# SCH_PCB-BRAILLE_2026-09-01.net
KiCad netlist of a schematic drawn in EasyEDA
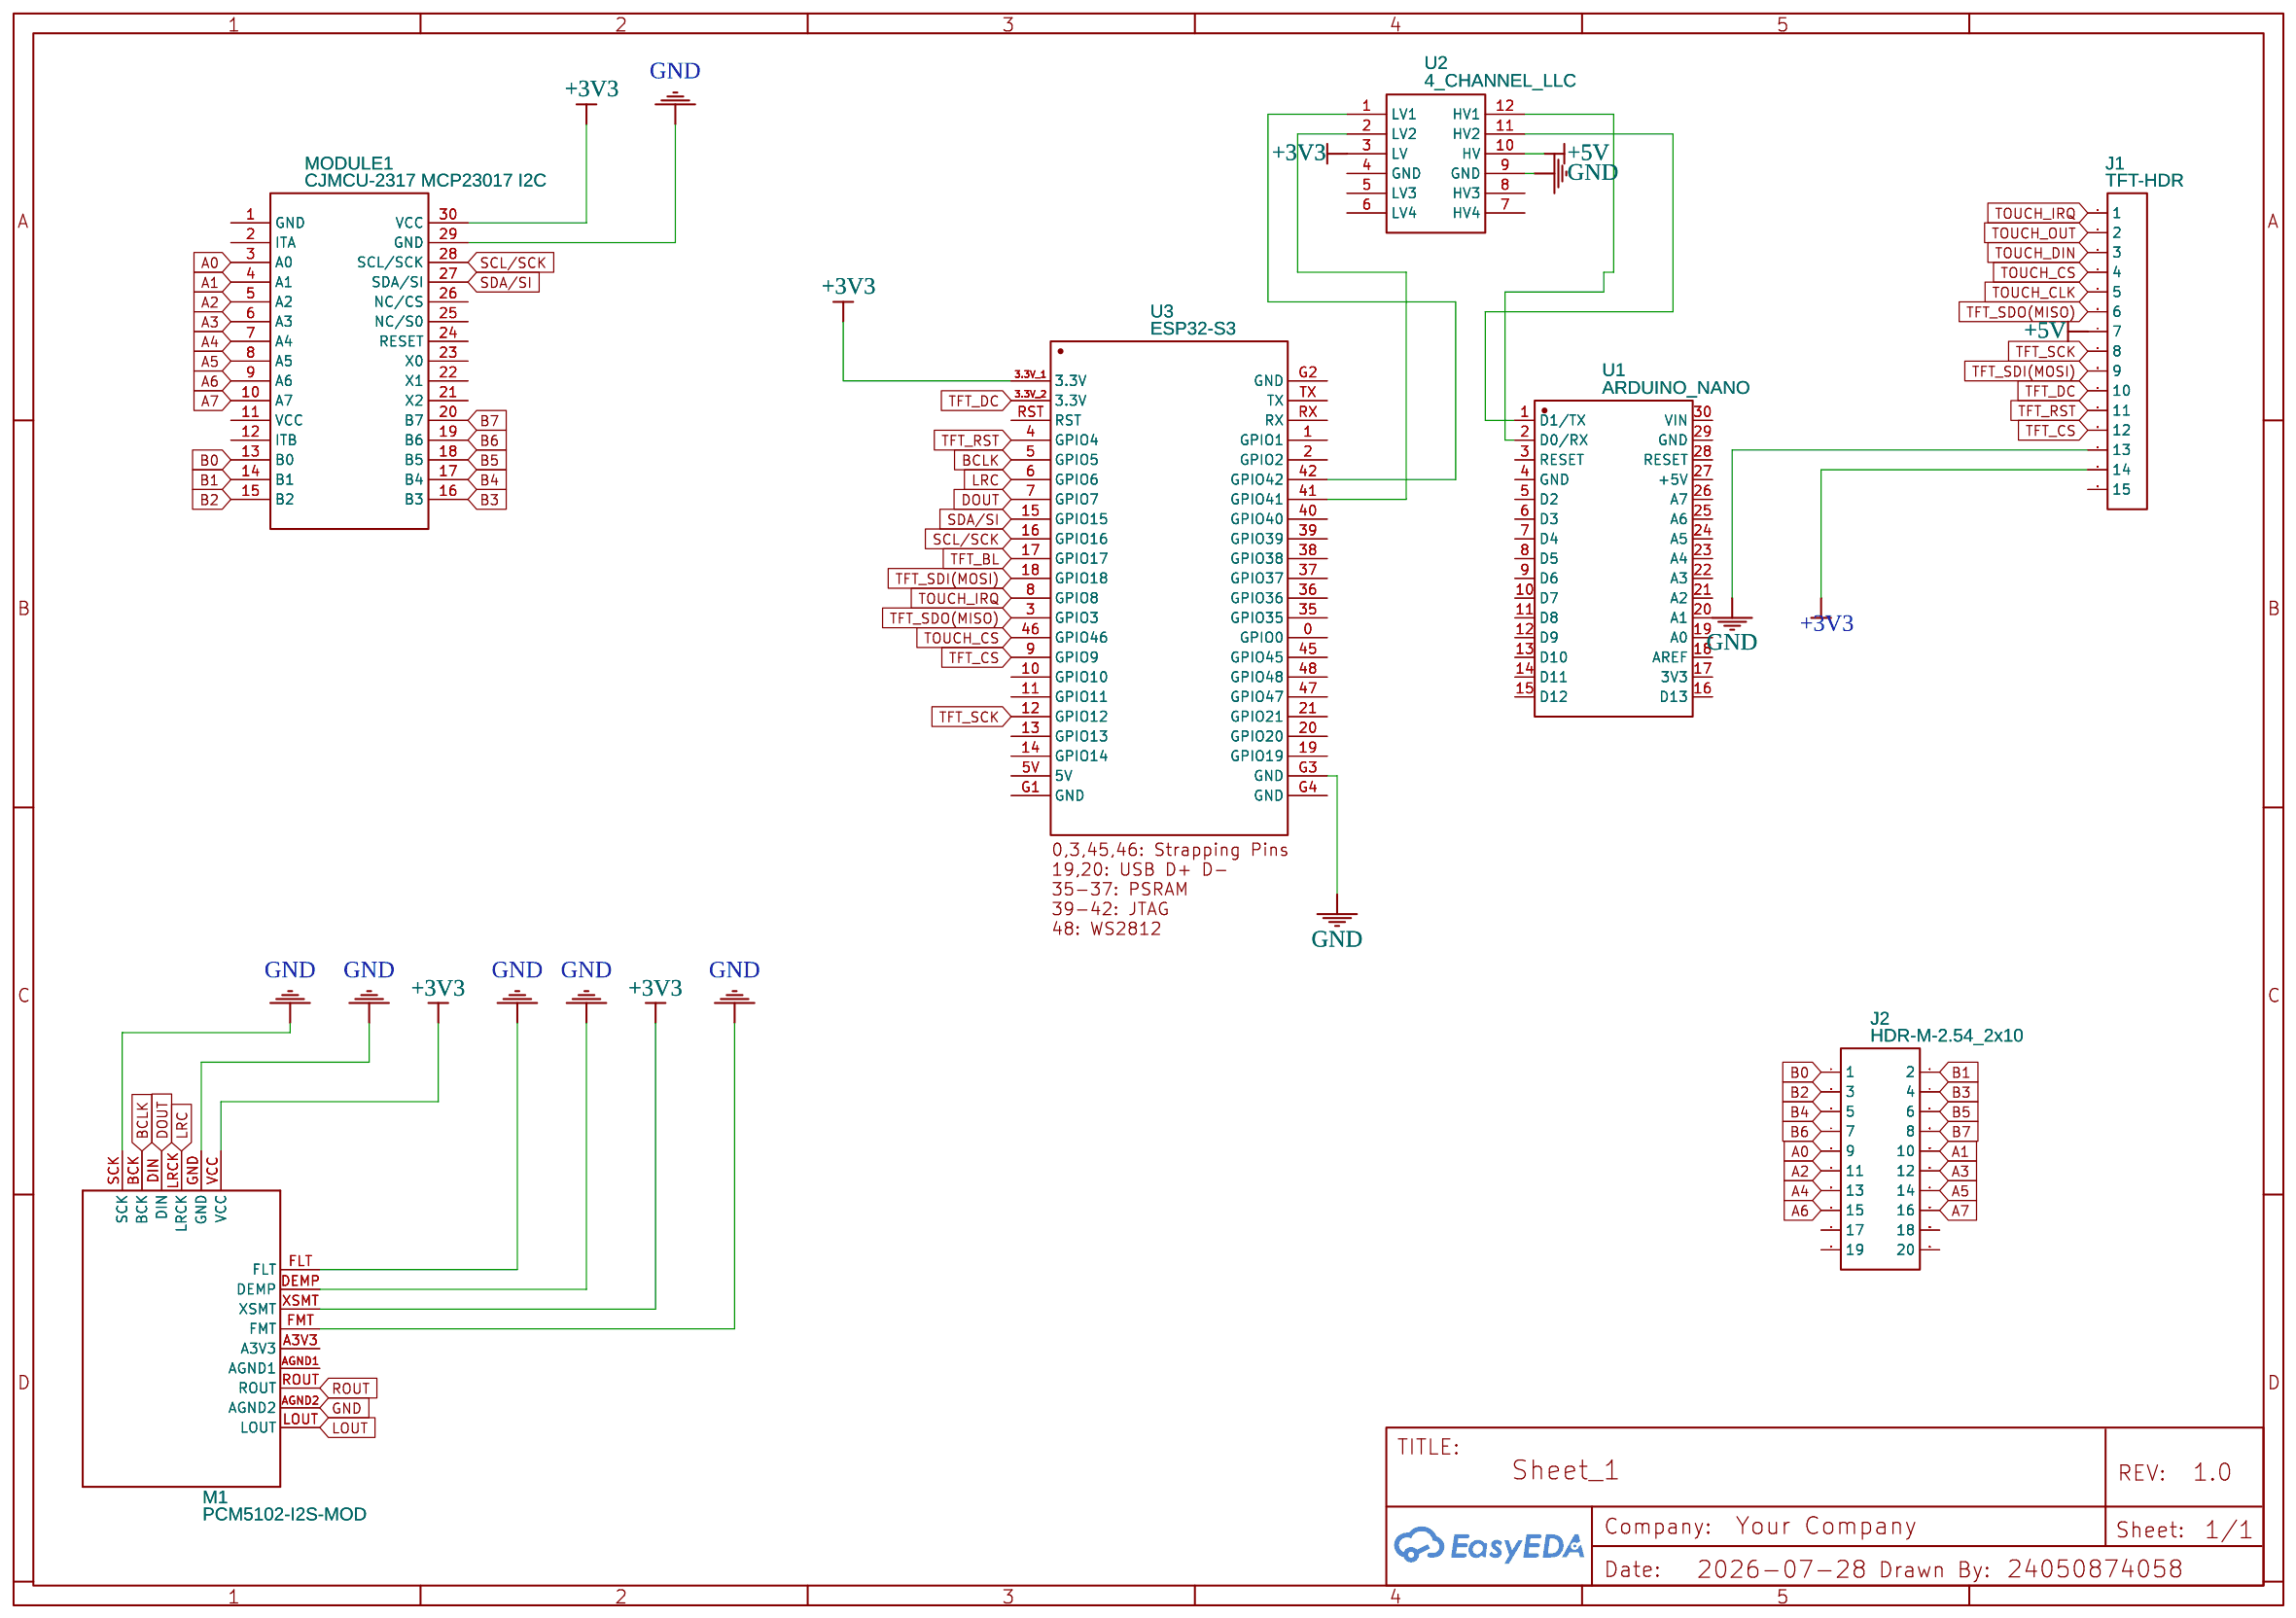
[diagram p0: schematic sheet]

(export (version "E")
  (design (tool "Eeschema 10.0.6"))
  (components
    (comp (ref "J1") (value "TFT-HDR") (libsource (lib "") (part "HDR-M-2.54_1x15")))
    (comp (ref "J2") (value "HDR-M-2.54_2x10") (libsource (lib "") (part "HDR-M-2.54_2x10")))
    (comp (ref "M1") (value "PCM5102-I2S-MOD") (libsource (lib "") (part "PCM5102-I2S-MOD")))
    (comp (ref "MODULE1")
      (value "CJMCU-2317 MCP23017 I2C")
      (libsource (lib "") (part "CJMCU-2317 MCP23017 I2C Serial Interface 16 bit I/O Expander Serial Module"))
    )
    (comp (ref "U1") (value "ARDUINO_NANO") (libsource (lib "") (part "ARDUINO_NANO")))
    (comp (ref "U2") (value "4_CHANNEL_LLC") (libsource (lib "") (part "4_CHANNEL_LLC")))
    (comp (ref "U3") (value "ESP32-S3") (libsource (lib "") (part "ESP32-S3")))
  )
  (nets
    (net (code "1") (name "+3V3") (class "Default")
      (node (ref "J1") (pin "14") (pinfunction "14_14") (pintype "unspecified"))
      (node (ref "M1") (pin "VCC") (pinfunction "VCC_VCC") (pintype "bidirectional"))
      (node (ref "M1") (pin "XSMT") (pinfunction "XSMT_XSMT") (pintype "bidirectional"))
      (node (ref "MODULE1") (pin "30") (pinfunction "VCC_30") (pintype "unspecified"))
      (node (ref "U2") (pin "3") (pinfunction "LV_3") (pintype "unspecified"))
      (node (ref "U3") (pin "3.3V_1") (pinfunction "3.3V_3.3V_1") (pintype "bidirectional"))
    )
    (net (code "2") (name "+5V") (class "Default")
      (node (ref "J1") (pin "7") (pinfunction "7_7") (pintype "unspecified"))
      (node (ref "U2") (pin "10") (pinfunction "HV_10") (pintype "unspecified"))
    )
    (net (code "3") (name "A0") (class "Default")
      (node (ref "J2") (pin "9") (pinfunction "9_9") (pintype "unspecified"))
      (node (ref "MODULE1") (pin "3") (pinfunction "A0_3") (pintype "unspecified"))
    )
    (net (code "4") (name "A1") (class "Default")
      (node (ref "J2") (pin "10") (pinfunction "10_10") (pintype "unspecified"))
      (node (ref "MODULE1") (pin "4") (pinfunction "A1_4") (pintype "unspecified"))
    )
    (net (code "5") (name "A2") (class "Default")
      (node (ref "J2") (pin "11") (pinfunction "11_11") (pintype "unspecified"))
      (node (ref "MODULE1") (pin "5") (pinfunction "A2_5") (pintype "unspecified"))
    )
    (net (code "6") (name "A3") (class "Default")
      (node (ref "J2") (pin "12") (pinfunction "12_12") (pintype "unspecified"))
      (node (ref "MODULE1") (pin "6") (pinfunction "A3_6") (pintype "unspecified"))
    )
    (net (code "7") (name "A4") (class "Default")
      (node (ref "J2") (pin "13") (pinfunction "13_13") (pintype "unspecified"))
      (node (ref "MODULE1") (pin "7") (pinfunction "A4_7") (pintype "unspecified"))
    )
    (net (code "8") (name "A5") (class "Default")
      (node (ref "J2") (pin "14") (pinfunction "14_14") (pintype "unspecified"))
      (node (ref "MODULE1") (pin "8") (pinfunction "A5_8") (pintype "unspecified"))
    )
    (net (code "9") (name "A6") (class "Default")
      (node (ref "J2") (pin "15") (pinfunction "15_15") (pintype "unspecified"))
      (node (ref "MODULE1") (pin "9") (pinfunction "A6_9") (pintype "unspecified"))
    )
    (net (code "10") (name "A7") (class "Default")
      (node (ref "J2") (pin "16") (pinfunction "16_16") (pintype "unspecified"))
      (node (ref "MODULE1") (pin "10") (pinfunction "A7_10") (pintype "unspecified"))
    )
    (net (code "11") (name "B0") (class "Default")
      (node (ref "J2") (pin "1") (pinfunction "1_1") (pintype "unspecified"))
      (node (ref "MODULE1") (pin "13") (pinfunction "B0_13") (pintype "unspecified"))
    )
    (net (code "12") (name "B1") (class "Default")
      (node (ref "J2") (pin "2") (pinfunction "2_2") (pintype "unspecified"))
      (node (ref "MODULE1") (pin "14") (pinfunction "B1_14") (pintype "unspecified"))
    )
    (net (code "13") (name "B2") (class "Default")
      (node (ref "J2") (pin "3") (pinfunction "3_3") (pintype "unspecified"))
      (node (ref "MODULE1") (pin "15") (pinfunction "B2_15") (pintype "unspecified"))
    )
    (net (code "14") (name "B3") (class "Default")
      (node (ref "J2") (pin "4") (pinfunction "4_4") (pintype "unspecified"))
      (node (ref "MODULE1") (pin "16") (pinfunction "B3_16") (pintype "unspecified"))
    )
    (net (code "15") (name "B4") (class "Default")
      (node (ref "J2") (pin "5") (pinfunction "5_5") (pintype "unspecified"))
      (node (ref "MODULE1") (pin "17") (pinfunction "B4_17") (pintype "unspecified"))
    )
    (net (code "16") (name "B5") (class "Default")
      (node (ref "J2") (pin "6") (pinfunction "6_6") (pintype "unspecified"))
      (node (ref "MODULE1") (pin "18") (pinfunction "B5_18") (pintype "unspecified"))
    )
    (net (code "17") (name "B6") (class "Default")
      (node (ref "J2") (pin "7") (pinfunction "7_7") (pintype "unspecified"))
      (node (ref "MODULE1") (pin "19") (pinfunction "B6_19") (pintype "unspecified"))
    )
    (net (code "18") (name "B7") (class "Default")
      (node (ref "J2") (pin "8") (pinfunction "8_8") (pintype "unspecified"))
      (node (ref "MODULE1") (pin "20") (pinfunction "B7_20") (pintype "unspecified"))
    )
    (net (code "19") (name "BCLK") (class "Default")
      (node (ref "M1") (pin "BCK") (pinfunction "BCK_BCK") (pintype "bidirectional"))
      (node (ref "U3") (pin "5") (pinfunction "GPIO5_5") (pintype "bidirectional"))
    )
    (net (code "20") (name "DOUT") (class "Default")
      (node (ref "M1") (pin "DIN") (pinfunction "DIN_DIN") (pintype "bidirectional"))
      (node (ref "U3") (pin "7") (pinfunction "GPIO7_7") (pintype "bidirectional"))
    )
    (net (code "21") (name "GND") (class "Default")
      (node (ref "J1") (pin "13") (pinfunction "13_13") (pintype "unspecified"))
      (node (ref "M1") (pin "AGND2") (pinfunction "AGND2_AGND2") (pintype "bidirectional"))
      (node (ref "M1") (pin "DEMP") (pinfunction "DEMP_DEMP") (pintype "bidirectional"))
      (node (ref "M1") (pin "FLT") (pinfunction "FLT_FLT") (pintype "bidirectional"))
      (node (ref "M1") (pin "FMT") (pinfunction "FMT_FMT") (pintype "bidirectional"))
      (node (ref "M1") (pin "GND") (pinfunction "GND_GND") (pintype "bidirectional"))
      (node (ref "M1") (pin "SCK") (pinfunction "SCK_SCK") (pintype "bidirectional"))
      (node (ref "MODULE1") (pin "29") (pinfunction "GND_29") (pintype "unspecified"))
      (node (ref "U2") (pin "9") (pinfunction "GND_9") (pintype "unspecified"))
      (node (ref "U3") (pin "G3") (pinfunction "GND_G3") (pintype "bidirectional"))
    )
    (net (code "22") (name "LOUT") (class "Default")
      (node (ref "M1") (pin "LOUT") (pinfunction "LOUT_LOUT") (pintype "bidirectional"))
    )
    (net (code "23") (name "LRC") (class "Default")
      (node (ref "M1") (pin "LRCK") (pinfunction "LRCK_LRCK") (pintype "bidirectional"))
      (node (ref "U3") (pin "6") (pinfunction "GPIO6_6") (pintype "bidirectional"))
    )
    (net (code "24") (name "Net-(U1-D0{slash}RX)") (class "Default")
      (node (ref "U1") (pin "2") (pinfunction "D0/RX_2") (pintype "unspecified"))
      (node (ref "U2") (pin "12") (pinfunction "HV1_12") (pintype "unspecified"))
    )
    (net (code "25") (name "Net-(U1-D1{slash}TX)") (class "Default")
      (node (ref "U1") (pin "1") (pinfunction "D1/TX_1") (pintype "unspecified"))
      (node (ref "U2") (pin "11") (pinfunction "HV2_11") (pintype "unspecified"))
    )
    (net (code "26") (name "Net-(U2-LV1)") (class "Default")
      (node (ref "U2") (pin "1") (pinfunction "LV1_1") (pintype "unspecified"))
      (node (ref "U3") (pin "42") (pinfunction "GPIO42_42") (pintype "bidirectional"))
    )
    (net (code "27") (name "Net-(U2-LV2)") (class "Default")
      (node (ref "U2") (pin "2") (pinfunction "LV2_2") (pintype "unspecified"))
      (node (ref "U3") (pin "41") (pinfunction "GPIO41_41") (pintype "bidirectional"))
    )
    (net (code "28") (name "ROUT") (class "Default")
      (node (ref "M1") (pin "ROUT") (pinfunction "ROUT_ROUT") (pintype "bidirectional"))
    )
    (net (code "29") (name "SCL{slash}SCK") (class "Default")
      (node (ref "MODULE1") (pin "28") (pinfunction "SCL/SCK_28") (pintype "unspecified"))
      (node (ref "U3") (pin "16") (pinfunction "GPIO16_16") (pintype "bidirectional"))
    )
    (net (code "30") (name "SDA{slash}SI") (class "Default")
      (node (ref "MODULE1") (pin "27") (pinfunction "SDA/SI_27") (pintype "unspecified"))
      (node (ref "U3") (pin "15") (pinfunction "GPIO15_15") (pintype "bidirectional"))
    )
    (net (code "31") (name "TFT_BL") (class "Default")
      (node (ref "U3") (pin "17") (pinfunction "GPIO17_17") (pintype "bidirectional"))
    )
    (net (code "32") (name "TFT_CS") (class "Default")
      (node (ref "J1") (pin "12") (pinfunction "12_12") (pintype "unspecified"))
      (node (ref "U3") (pin "9") (pinfunction "GPIO9_9") (pintype "bidirectional"))
    )
    (net (code "33") (name "TFT_DC") (class "Default")
      (node (ref "J1") (pin "10") (pinfunction "10_10") (pintype "unspecified"))
      (node (ref "U3") (pin "3.3V_2") (pinfunction "3.3V_3.3V_2") (pintype "bidirectional"))
    )
    (net (code "34") (name "TFT_RST") (class "Default")
      (node (ref "J1") (pin "11") (pinfunction "11_11") (pintype "unspecified"))
      (node (ref "U3") (pin "4") (pinfunction "GPIO4_4") (pintype "bidirectional"))
    )
    (net (code "35") (name "TFT_SCK") (class "Default")
      (node (ref "J1") (pin "8") (pinfunction "8_8") (pintype "unspecified"))
      (node (ref "U3") (pin "12") (pinfunction "GPIO12_12") (pintype "bidirectional"))
    )
    (net (code "36") (name "TFT_SDI(MOSI)") (class "Default")
      (node (ref "J1") (pin "9") (pinfunction "9_9") (pintype "unspecified"))
      (node (ref "U3") (pin "18") (pinfunction "GPIO18_18") (pintype "bidirectional"))
    )
    (net (code "37") (name "TFT_SDO(MISO)") (class "Default")
      (node (ref "J1") (pin "6") (pinfunction "6_6") (pintype "unspecified"))
      (node (ref "U3") (pin "3") (pinfunction "GPIO3_3") (pintype "bidirectional"))
    )
    (net (code "38") (name "TOUCH_CLK") (class "Default")
      (node (ref "J1") (pin "5") (pinfunction "5_5") (pintype "unspecified"))
    )
    (net (code "39") (name "TOUCH_CS") (class "Default")
      (node (ref "J1") (pin "4") (pinfunction "4_4") (pintype "unspecified"))
      (node (ref "U3") (pin "46") (pinfunction "GPIO46_46") (pintype "bidirectional"))
    )
    (net (code "40") (name "TOUCH_DIN") (class "Default")
      (node (ref "J1") (pin "3") (pinfunction "3_3") (pintype "unspecified"))
    )
    (net (code "41") (name "TOUCH_IRQ") (class "Default")
      (node (ref "J1") (pin "1") (pinfunction "1_1") (pintype "unspecified"))
      (node (ref "U3") (pin "8") (pinfunction "GPIO8_8") (pintype "bidirectional"))
    )
    (net (code "42") (name "TOUCH_OUT") (class "Default")
      (node (ref "J1") (pin "2") (pinfunction "2_2") (pintype "unspecified"))
    )
    (net (code "43") (name "unconnected-(J1-Pad15)") (class "Default")
      (node (ref "J1") (pin "15") (pinfunction "15_15") (pintype "unspecified"))
    )
    (net (code "44") (name "unconnected-(J2-Pad17)") (class "Default")
      (node (ref "J2") (pin "17") (pinfunction "17_17") (pintype "unspecified"))
    )
    (net (code "45") (name "unconnected-(J2-Pad18)") (class "Default")
      (node (ref "J2") (pin "18") (pinfunction "18_18") (pintype "unspecified"))
    )
    (net (code "46") (name "unconnected-(J2-Pad19)") (class "Default")
      (node (ref "J2") (pin "19") (pinfunction "19_19") (pintype "unspecified"))
    )
    (net (code "47") (name "unconnected-(J2-Pad20)") (class "Default")
      (node (ref "J2") (pin "20") (pinfunction "20_20") (pintype "unspecified"))
    )
    (net (code "48") (name "unconnected-(M1-PadA3V3)") (class "Default")
      (node (ref "M1") (pin "A3V3") (pinfunction "A3V3_A3V3") (pintype "bidirectional"))
    )
    (net (code "49") (name "unconnected-(M1-PadAGND1)") (class "Default")
      (node (ref "M1") (pin "AGND1") (pinfunction "AGND1_AGND1") (pintype "bidirectional"))
    )
    (net (code "50") (name "unconnected-(MODULE1-GND-Pad1)") (class "Default")
      (node (ref "MODULE1") (pin "1") (pinfunction "GND_1") (pintype "unspecified"))
    )
    (net (code "51") (name "unconnected-(MODULE1-ITA-Pad2)") (class "Default")
      (node (ref "MODULE1") (pin "2") (pinfunction "ITA_2") (pintype "unspecified"))
    )
    (net (code "52") (name "unconnected-(MODULE1-ITB-Pad12)") (class "Default")
      (node (ref "MODULE1") (pin "12") (pinfunction "ITB_12") (pintype "unspecified"))
    )
    (net (code "53") (name "unconnected-(MODULE1-NC{slash}CS-Pad26)") (class "Default")
      (node (ref "MODULE1") (pin "26") (pinfunction "NC/CS_26") (pintype "unspecified"))
    )
    (net (code "54") (name "unconnected-(MODULE1-NC{slash}S0-Pad25)") (class "Default")
      (node (ref "MODULE1") (pin "25") (pinfunction "NC/S0_25") (pintype "unspecified"))
    )
    (net (code "55") (name "unconnected-(MODULE1-RESET-Pad24)") (class "Default")
      (node (ref "MODULE1") (pin "24") (pinfunction "RESET_24") (pintype "unspecified"))
    )
    (net (code "56") (name "unconnected-(MODULE1-VCC-Pad11)") (class "Default")
      (node (ref "MODULE1") (pin "11") (pinfunction "VCC_11") (pintype "unspecified"))
    )
    (net (code "57") (name "unconnected-(MODULE1-X0-Pad23)") (class "Default")
      (node (ref "MODULE1") (pin "23") (pinfunction "X0_23") (pintype "unspecified"))
    )
    (net (code "58") (name "unconnected-(MODULE1-X1-Pad22)") (class "Default")
      (node (ref "MODULE1") (pin "22") (pinfunction "X1_22") (pintype "unspecified"))
    )
    (net (code "59") (name "unconnected-(MODULE1-X2-Pad21)") (class "Default")
      (node (ref "MODULE1") (pin "21") (pinfunction "X2_21") (pintype "unspecified"))
    )
    (net (code "60") (name "unconnected-(U1-+5V-Pad27)") (class "Default")
      (node (ref "U1") (pin "27") (pinfunction "+5V_27") (pintype "unspecified"))
    )
    (net (code "61") (name "unconnected-(U1-3V3-Pad17)") (class "Default")
      (node (ref "U1") (pin "17") (pinfunction "3V3_17") (pintype "unspecified"))
    )
    (net (code "62") (name "unconnected-(U1-A0-Pad19)") (class "Default")
      (node (ref "U1") (pin "19") (pinfunction "A0_19") (pintype "unspecified"))
    )
    (net (code "63") (name "unconnected-(U1-A1-Pad20)") (class "Default")
      (node (ref "U1") (pin "20") (pinfunction "A1_20") (pintype "unspecified"))
    )
    (net (code "64") (name "unconnected-(U1-A2-Pad21)") (class "Default")
      (node (ref "U1") (pin "21") (pinfunction "A2_21") (pintype "unspecified"))
    )
    (net (code "65") (name "unconnected-(U1-A3-Pad22)") (class "Default")
      (node (ref "U1") (pin "22") (pinfunction "A3_22") (pintype "unspecified"))
    )
    (net (code "66") (name "unconnected-(U1-A4-Pad23)") (class "Default")
      (node (ref "U1") (pin "23") (pinfunction "A4_23") (pintype "unspecified"))
    )
    (net (code "67") (name "unconnected-(U1-A5-Pad24)") (class "Default")
      (node (ref "U1") (pin "24") (pinfunction "A5_24") (pintype "unspecified"))
    )
    (net (code "68") (name "unconnected-(U1-A6-Pad25)") (class "Default")
      (node (ref "U1") (pin "25") (pinfunction "A6_25") (pintype "unspecified"))
    )
    (net (code "69") (name "unconnected-(U1-A7-Pad26)") (class "Default")
      (node (ref "U1") (pin "26") (pinfunction "A7_26") (pintype "unspecified"))
    )
    (net (code "70") (name "unconnected-(U1-AREF-Pad18)") (class "Default")
      (node (ref "U1") (pin "18") (pinfunction "AREF_18") (pintype "unspecified"))
    )
    (net (code "71") (name "unconnected-(U1-D2-Pad5)") (class "Default")
      (node (ref "U1") (pin "5") (pinfunction "D2_5") (pintype "unspecified"))
    )
    (net (code "72") (name "unconnected-(U1-D3-Pad6)") (class "Default")
      (node (ref "U1") (pin "6") (pinfunction "D3_6") (pintype "unspecified"))
    )
    (net (code "73") (name "unconnected-(U1-D4-Pad7)") (class "Default")
      (node (ref "U1") (pin "7") (pinfunction "D4_7") (pintype "unspecified"))
    )
    (net (code "74") (name "unconnected-(U1-D5-Pad8)") (class "Default")
      (node (ref "U1") (pin "8") (pinfunction "D5_8") (pintype "unspecified"))
    )
    (net (code "75") (name "unconnected-(U1-D6-Pad9)") (class "Default")
      (node (ref "U1") (pin "9") (pinfunction "D6_9") (pintype "unspecified"))
    )
    (net (code "76") (name "unconnected-(U1-D7-Pad10)") (class "Default")
      (node (ref "U1") (pin "10") (pinfunction "D7_10") (pintype "unspecified"))
    )
    (net (code "77") (name "unconnected-(U1-D8-Pad11)") (class "Default")
      (node (ref "U1") (pin "11") (pinfunction "D8_11") (pintype "unspecified"))
    )
    (net (code "78") (name "unconnected-(U1-D9-Pad12)") (class "Default")
      (node (ref "U1") (pin "12") (pinfunction "D9_12") (pintype "unspecified"))
    )
    (net (code "79") (name "unconnected-(U1-D10-Pad13)") (class "Default")
      (node (ref "U1") (pin "13") (pinfunction "D10_13") (pintype "unspecified"))
    )
    (net (code "80") (name "unconnected-(U1-D11-Pad14)") (class "Default")
      (node (ref "U1") (pin "14") (pinfunction "D11_14") (pintype "unspecified"))
    )
    (net (code "81") (name "unconnected-(U1-D12-Pad15)") (class "Default")
      (node (ref "U1") (pin "15") (pinfunction "D12_15") (pintype "unspecified"))
    )
    (net (code "82") (name "unconnected-(U1-D13-Pad16)") (class "Default")
      (node (ref "U1") (pin "16") (pinfunction "D13_16") (pintype "unspecified"))
    )
    (net (code "83") (name "unconnected-(U1-GND-Pad4)") (class "Default")
      (node (ref "U1") (pin "4") (pinfunction "GND_4") (pintype "unspecified"))
    )
    (net (code "84") (name "unconnected-(U1-GND-Pad29)") (class "Default")
      (node (ref "U1") (pin "29") (pinfunction "GND_29") (pintype "unspecified"))
    )
    (net (code "85") (name "unconnected-(U1-RESET-Pad3)") (class "Default")
      (node (ref "U1") (pin "3") (pinfunction "RESET_3") (pintype "unspecified"))
    )
    (net (code "86") (name "unconnected-(U1-RESET-Pad28)") (class "Default")
      (node (ref "U1") (pin "28") (pinfunction "RESET_28") (pintype "unspecified"))
    )
    (net (code "87") (name "unconnected-(U1-VIN-Pad30)") (class "Default")
      (node (ref "U1") (pin "30") (pinfunction "VIN_30") (pintype "unspecified"))
    )
    (net (code "88") (name "unconnected-(U2-GND-Pad4)") (class "Default")
      (node (ref "U2") (pin "4") (pinfunction "GND_4") (pintype "unspecified"))
    )
    (net (code "89") (name "unconnected-(U2-HV3-Pad8)") (class "Default")
      (node (ref "U2") (pin "8") (pinfunction "HV3_8") (pintype "unspecified"))
    )
    (net (code "90") (name "unconnected-(U2-HV4-Pad7)") (class "Default")
      (node (ref "U2") (pin "7") (pinfunction "HV4_7") (pintype "unspecified"))
    )
    (net (code "91") (name "unconnected-(U2-LV3-Pad5)") (class "Default")
      (node (ref "U2") (pin "5") (pinfunction "LV3_5") (pintype "unspecified"))
    )
    (net (code "92") (name "unconnected-(U2-LV4-Pad6)") (class "Default")
      (node (ref "U2") (pin "6") (pinfunction "LV4_6") (pintype "unspecified"))
    )
    (net (code "93") (name "unconnected-(U3-GND-PadG1)") (class "Default")
      (node (ref "U3") (pin "G1") (pinfunction "GND_G1") (pintype "bidirectional"))
    )
    (net (code "94") (name "unconnected-(U3-GND-PadG2)") (class "Default")
      (node (ref "U3") (pin "G2") (pinfunction "GND_G2") (pintype "bidirectional"))
    )
    (net (code "95") (name "unconnected-(U3-GND-PadG4)") (class "Default")
      (node (ref "U3") (pin "G4") (pinfunction "GND_G4") (pintype "bidirectional"))
    )
    (net (code "96") (name "unconnected-(U3-GPIO0-Pad0)") (class "Default")
      (node (ref "U3") (pin "0") (pinfunction "GPIO0_0") (pintype "bidirectional"))
    )
    (net (code "97") (name "unconnected-(U3-GPIO1-Pad1)") (class "Default")
      (node (ref "U3") (pin "1") (pinfunction "GPIO1_1") (pintype "bidirectional"))
    )
    (net (code "98") (name "unconnected-(U3-GPIO2-Pad2)") (class "Default")
      (node (ref "U3") (pin "2") (pinfunction "GPIO2_2") (pintype "bidirectional"))
    )
    (net (code "99") (name "unconnected-(U3-GPIO10-Pad10)") (class "Default")
      (node (ref "U3") (pin "10") (pinfunction "GPIO10_10") (pintype "bidirectional"))
    )
    (net (code "100") (name "unconnected-(U3-GPIO11-Pad11)") (class "Default")
      (node (ref "U3") (pin "11") (pinfunction "GPIO11_11") (pintype "bidirectional"))
    )
    (net (code "101") (name "unconnected-(U3-GPIO13-Pad13)") (class "Default")
      (node (ref "U3") (pin "13") (pinfunction "GPIO13_13") (pintype "bidirectional"))
    )
    (net (code "102") (name "unconnected-(U3-GPIO14-Pad14)") (class "Default")
      (node (ref "U3") (pin "14") (pinfunction "GPIO14_14") (pintype "bidirectional"))
    )
    (net (code "103") (name "unconnected-(U3-GPIO19-Pad19)") (class "Default")
      (node (ref "U3") (pin "19") (pinfunction "GPIO19_19") (pintype "bidirectional"))
    )
    (net (code "104") (name "unconnected-(U3-GPIO20-Pad20)") (class "Default")
      (node (ref "U3") (pin "20") (pinfunction "GPIO20_20") (pintype "bidirectional"))
    )
    (net (code "105") (name "unconnected-(U3-GPIO21-Pad21)") (class "Default")
      (node (ref "U3") (pin "21") (pinfunction "GPIO21_21") (pintype "bidirectional"))
    )
    (net (code "106") (name "unconnected-(U3-GPIO35-Pad35)") (class "Default")
      (node (ref "U3") (pin "35") (pinfunction "GPIO35_35") (pintype "bidirectional"))
    )
    (net (code "107") (name "unconnected-(U3-GPIO36-Pad36)") (class "Default")
      (node (ref "U3") (pin "36") (pinfunction "GPIO36_36") (pintype "bidirectional"))
    )
    (net (code "108") (name "unconnected-(U3-GPIO37-Pad37)") (class "Default")
      (node (ref "U3") (pin "37") (pinfunction "GPIO37_37") (pintype "bidirectional"))
    )
    (net (code "109") (name "unconnected-(U3-GPIO38-Pad38)") (class "Default")
      (node (ref "U3") (pin "38") (pinfunction "GPIO38_38") (pintype "bidirectional"))
    )
    (net (code "110") (name "unconnected-(U3-GPIO39-Pad39)") (class "Default")
      (node (ref "U3") (pin "39") (pinfunction "GPIO39_39") (pintype "bidirectional"))
    )
    (net (code "111") (name "unconnected-(U3-GPIO40-Pad40)") (class "Default")
      (node (ref "U3") (pin "40") (pinfunction "GPIO40_40") (pintype "bidirectional"))
    )
    (net (code "112") (name "unconnected-(U3-GPIO45-Pad45)") (class "Default")
      (node (ref "U3") (pin "45") (pinfunction "GPIO45_45") (pintype "bidirectional"))
    )
    (net (code "113") (name "unconnected-(U3-GPIO47-Pad47)") (class "Default")
      (node (ref "U3") (pin "47") (pinfunction "GPIO47_47") (pintype "bidirectional"))
    )
    (net (code "114") (name "unconnected-(U3-GPIO48-Pad48)") (class "Default")
      (node (ref "U3") (pin "48") (pinfunction "GPIO48_48") (pintype "bidirectional"))
    )
    (net (code "115") (name "unconnected-(U3-Pad5V)") (class "Default")
      (node (ref "U3") (pin "5V") (pinfunction "5V_5V") (pintype "bidirectional"))
    )
    (net (code "116") (name "unconnected-(U3-PadRST)") (class "Default")
      (node (ref "U3") (pin "RST") (pinfunction "RST_RST") (pintype "bidirectional"))
    )
    (net (code "117") (name "unconnected-(U3-PadRX)") (class "Default")
      (node (ref "U3") (pin "RX") (pinfunction "RX_RX") (pintype "bidirectional"))
    )
    (net (code "118") (name "unconnected-(U3-PadTX)") (class "Default")
      (node (ref "U3") (pin "TX") (pinfunction "TX_TX") (pintype "bidirectional"))
    )
  )
)
